# laserboard.net
KiCad netlist of a schematic drawn in EAGLE
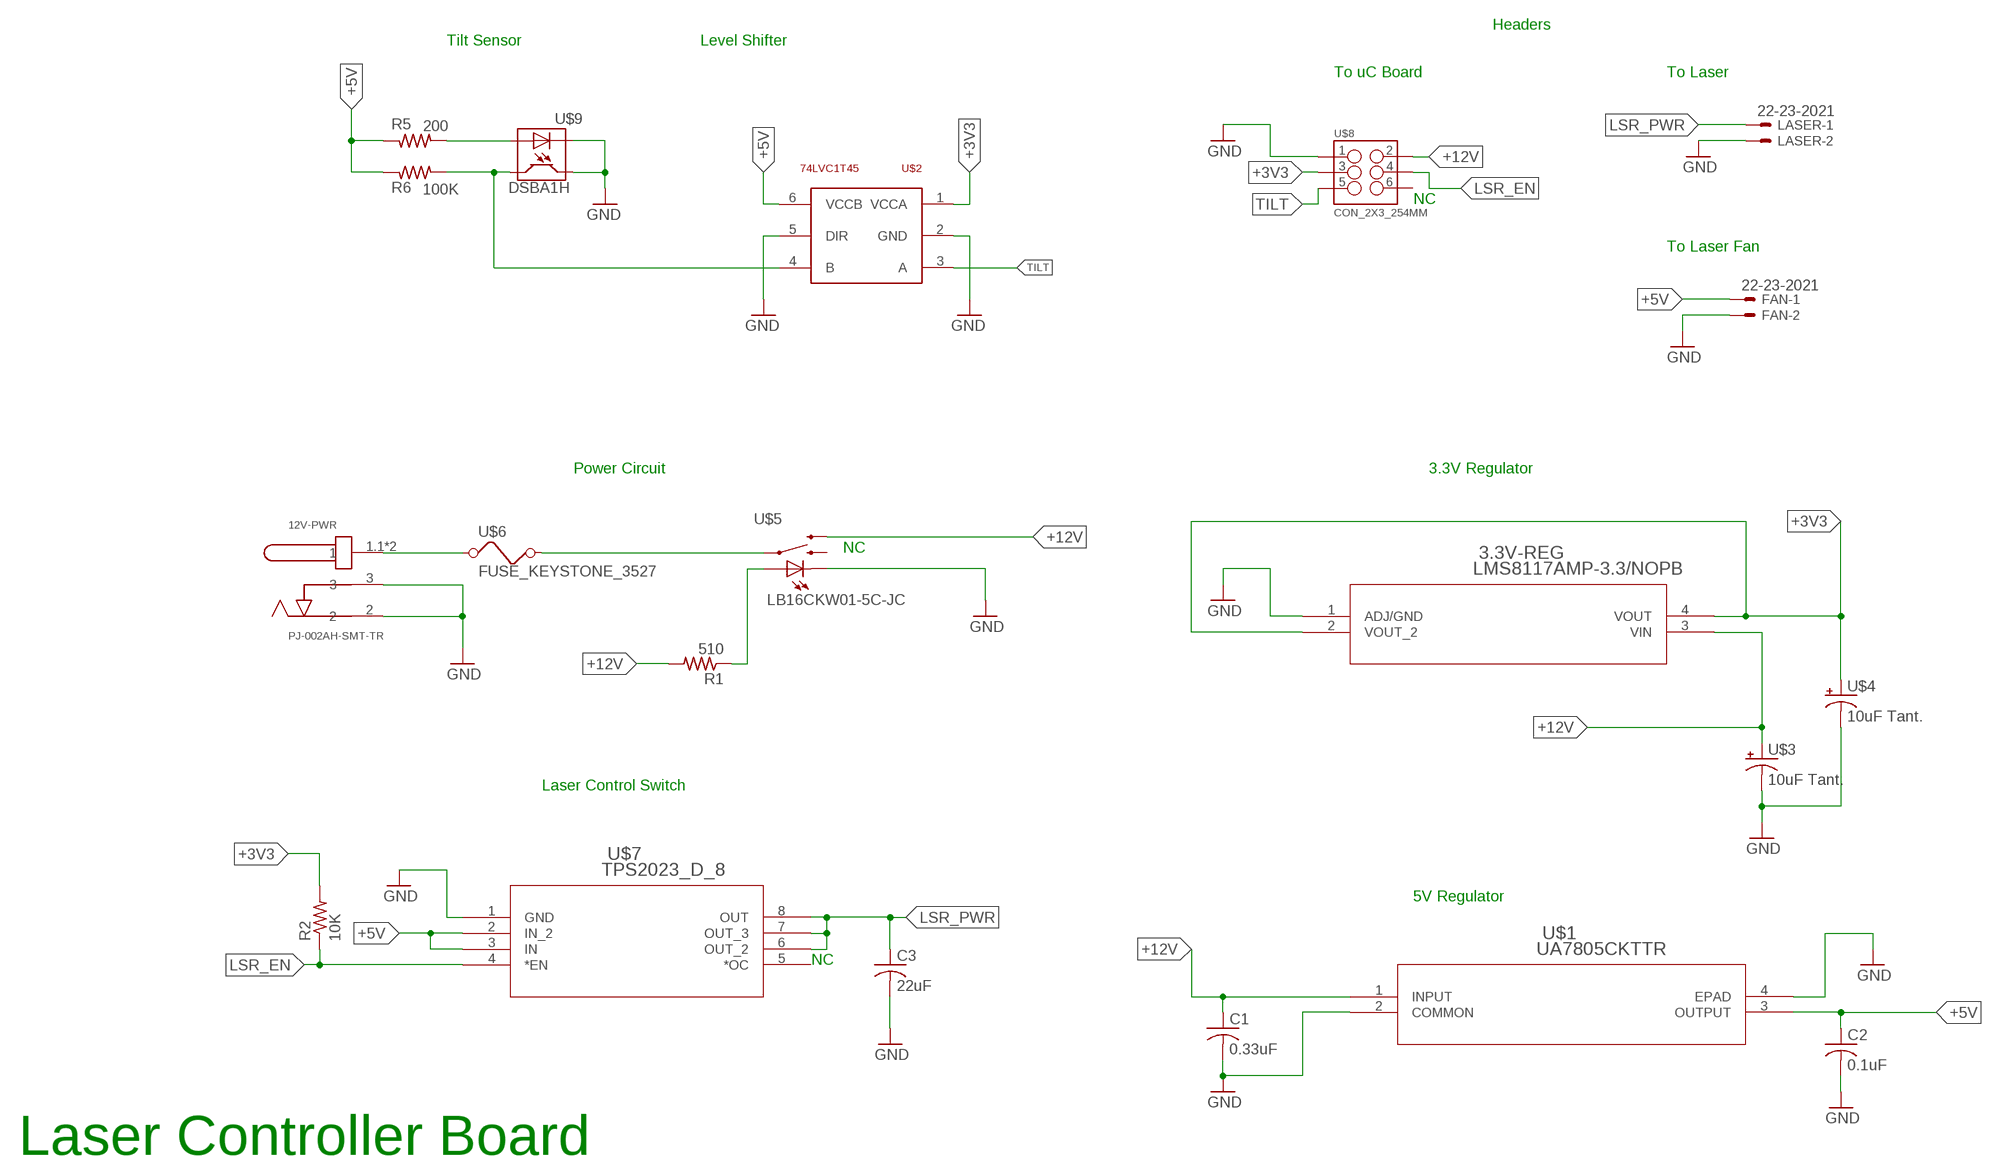
[diagram p0: schematic, sheet 1]

(export (version "E")
  (design (tool "Eeschema 10.0.6"))
  (components
    (comp (ref "3.3V-REG")
      (value "LMS8117AMP-3.3/NOPB")
      (footprint "eagle-import:MP04A")
      (fields
        (field (name "MANUFACTURER_PART_NUMBER") "LMS8117AMP-33")
        (field (name "COPYRIGHT") "Copyright (C) 2015 Accelerated Designs. All rights reserved")
      )
      (libsource (lib "eagle-import") (part "LMS8117AMP-3.3/NOPB"))
    )
    (comp (ref "12V-PWR")
      (value "PJ-002AH-SMT-TR")
      (footprint "eagle-import:CUI_PJ-002AH-SMT-TR")
      (libsource (lib "eagle-import") (part "PJ-002AH-SMT-TR"))
    )
    (comp (ref "C1")
      (value "0.33uF")
      (footprint "eagle-import:C0805")
      (libsource (lib "eagle-import") (part "C-USC0805"))
    )
    (comp (ref "C2")
      (value "0.1uF")
      (footprint "eagle-import:C0805")
      (libsource (lib "eagle-import") (part "C-USC0805"))
    )
    (comp (ref "C3")
      (value "22uF")
      (footprint "eagle-import:C0805")
      (libsource (lib "eagle-import") (part "C-USC0805"))
    )
    (comp (ref "FAN")
      (value "22-23-2021")
      (footprint "eagle-import:22-23-2021")
      (fields (field (name "MF") "MOLEX"))
      (libsource (lib "eagle-import") (part "22-23-2021"))
    )
    (comp (ref "LASER")
      (value "22-23-2021")
      (footprint "eagle-import:22-23-2021")
      (fields (field (name "MF") "MOLEX"))
      (libsource (lib "eagle-import") (part "22-23-2021"))
    )
    (comp (ref "R1")
      (value "510")
      (footprint "eagle-import:R0805")
      (libsource (lib "eagle-import") (part "R-US_R0805"))
    )
    (comp (ref "R2")
      (value "10K")
      (footprint "eagle-import:R0805")
      (libsource (lib "eagle-import") (part "R-US_R0805"))
    )
    (comp (ref "R5")
      (value "200")
      (footprint "eagle-import:R0805")
      (libsource (lib "eagle-import") (part "R-US_R0805"))
    )
    (comp (ref "R6")
      (value "100K")
      (footprint "eagle-import:R0805")
      (libsource (lib "eagle-import") (part "R-US_R0805"))
    )
    (comp (ref "U$1")
      (value "UA7805CKTTR")
      (footprint "eagle-import:KTT3_6P22X6P6")
      (fields
        (field (name "GENERIC_PART_NUMBER") "UA7805")
        (field (name "MANUFACTURER") "Texas Instruments")
        (field (name "MANUFACTURER_PART_NUMBER") "ua7805_ktt_3")
        (field (name "COPYRIGHT") "Copyright (C) 2015 Accelerated Designs. All rights reserved")
      )
      (libsource (lib "eagle-import") (part "UA7805CKTTR"))
    )
    (comp (ref "U$2")
      (value "74LVC1T45")
      (footprint "eagle-import:SOT363")
      (libsource (lib "eagle-import") (part "74LVC1T45"))
    )
    (comp (ref "U$3")
      (value "10uF Tant.")
      (footprint "eagle-import:C0805")
      (libsource (lib "eagle-import") (part "CAPACITOR_POL_0805"))
    )
    (comp (ref "U$4")
      (value "10uF Tant.")
      (footprint "eagle-import:C0805")
      (libsource (lib "eagle-import") (part "CAPACITOR_POL_0805"))
    )
    (comp (ref "U$5")
      (value "LB16CKW01-5C-JC")
      (footprint "eagle-import:LB16CKW01-5C-JC")
      (libsource (lib "eagle-import") (part "LB16CKW01-5C-JC"))
    )
    (comp (ref "U$6")
      (value "FUSE_KEYSTONE_3527")
      (footprint "eagle-import:KEYSTONE3527")
      (libsource (lib "eagle-import") (part "FUSE_KEYSTONE_3527"))
    )
    (comp (ref "U$7")
      (value "TPS2023_D_8")
      (footprint "eagle-import:D8")
      (fields
        (field (name "GENERIC_PART_NUMBER") "TPS2023")
        (field (name "MANUFACTURER") "Texas Instruments")
        (field (name "MANUFACTURER_PART_NUMBER") "tps2023_d_8")
        (field (name "COPYRIGHT") "Copyright (C) 2015 Accelerated Designs. All rights reserved")
      )
      (libsource (lib "eagle-import") (part "TPS2023_D_8"))
    )
    (comp (ref "U$8")
      (value "CON_2X3_254MM")
      (footprint "eagle-import:CON_2X3_254MM")
      (libsource (lib "eagle-import") (part "CON_2X3_254MM"))
    )
    (comp (ref "U$9")
      (value "DSBA1H")
      (footprint "eagle-import:DSBA1H")
      (libsource (lib "eagle-import") (part "DSBA1H"))
    )
  )
  (nets
    (net (code "1") (name "+3V3") (class "Default")
      (node (ref "3.3V-REG") (pin "2") (pinfunction "VOUT_2_2") (pintype "output"))
      (node (ref "3.3V-REG") (pin "4") (pinfunction "VOUT_4") (pintype "output"))
      (node (ref "R2") (pin "2") (pinfunction "2_2") (pintype "passive"))
      (node (ref "U$2") (pin "1") (pinfunction "VCCA_1") (pintype "bidirectional"))
      (node (ref "U$4") (pin "+") (pinfunction "+_+") (pintype "passive"))
      (node (ref "U$8") (pin "3") (pinfunction "3_3") (pintype "bidirectional"))
    )
    (net (code "2") (name "+5V") (class "Default")
      (node (ref "C2") (pin "1") (pinfunction "1_1") (pintype "passive"))
      (node (ref "FAN") (pin "1") (pinfunction "S_1") (pintype "passive"))
      (node (ref "R5") (pin "1") (pinfunction "1_1") (pintype "passive"))
      (node (ref "R6") (pin "1") (pinfunction "1_1") (pintype "passive"))
      (node (ref "U$1") (pin "3") (pinfunction "OUTPUT_3") (pintype "output"))
      (node (ref "U$2") (pin "6") (pinfunction "VCCB_6") (pintype "bidirectional"))
      (node (ref "U$7") (pin "2") (pinfunction "IN_2_2") (pintype "input"))
      (node (ref "U$7") (pin "3") (pinfunction "IN_3") (pintype "input"))
    )
    (net (code "3") (name "+12V") (class "Default")
      (node (ref "3.3V-REG") (pin "3") (pinfunction "VIN_3") (pintype "input"))
      (node (ref "C1") (pin "1") (pinfunction "1_1") (pintype "passive"))
      (node (ref "R1") (pin "2") (pinfunction "2_2") (pintype "passive"))
      (node (ref "U$1") (pin "1") (pinfunction "INPUT_1") (pintype "input"))
      (node (ref "U$3") (pin "+") (pinfunction "+_+") (pintype "passive"))
      (node (ref "U$5") (pin "2") (pinfunction "2_2") (pintype "passive"))
      (node (ref "U$8") (pin "2") (pinfunction "2_2") (pintype "bidirectional"))
    )
    (net (code "4") (name "GND") (class "Default")
      (node (ref "12V-PWR") (pin "2") (pinfunction "2_2") (pintype "passive"))
      (node (ref "12V-PWR") (pin "3") (pinfunction "3_3") (pintype "passive"))
      (node (ref "3.3V-REG") (pin "1") (pinfunction "ADJ/GND_1") (pintype "passive"))
      (node (ref "C1") (pin "2") (pinfunction "2_2") (pintype "passive"))
      (node (ref "C2") (pin "2") (pinfunction "2_2") (pintype "passive"))
      (node (ref "C3") (pin "2") (pinfunction "2_2") (pintype "passive"))
      (node (ref "FAN") (pin "2") (pinfunction "S_2") (pintype "passive"))
      (node (ref "LASER") (pin "2") (pinfunction "S_2") (pintype "passive"))
      (node (ref "U$1") (pin "2") (pinfunction "COMMON_2") (pintype "power_in"))
      (node (ref "U$1") (pin "4") (pinfunction "EPAD_4") (pintype "passive"))
      (node (ref "U$2") (pin "2") (pinfunction "GND_2") (pintype "bidirectional"))
      (node (ref "U$2") (pin "5") (pinfunction "DIR_5") (pintype "bidirectional"))
      (node (ref "U$3") (pin "-") (pinfunction "-_-") (pintype "passive"))
      (node (ref "U$4") (pin "-") (pinfunction "-_-") (pintype "passive"))
      (node (ref "U$5") (pin "-") (pinfunction "-_-") (pintype "passive"))
      (node (ref "U$7") (pin "1") (pinfunction "GND_1") (pintype "input"))
      (node (ref "U$8") (pin "1") (pinfunction "1_1") (pintype "bidirectional"))
      (node (ref "U$9") (pin "-") (pinfunction "-_-") (pintype "passive"))
      (node (ref "U$9") (pin "E") (pinfunction "E_E") (pintype "passive"))
    )
    (net (code "5") (name "LSR_EN") (class "Default")
      (node (ref "R2") (pin "1") (pinfunction "1_1") (pintype "passive"))
      (node (ref "U$7") (pin "4") (pinfunction "*EN_4") (pintype "input"))
      (node (ref "U$8") (pin "4") (pinfunction "4_4") (pintype "bidirectional"))
    )
    (net (code "6") (name "LSR_PWR") (class "Default")
      (node (ref "C3") (pin "1") (pinfunction "1_1") (pintype "passive"))
      (node (ref "LASER") (pin "1") (pinfunction "S_1") (pintype "passive"))
      (node (ref "U$7") (pin "6") (pinfunction "OUT_2_6") (pintype "output"))
      (node (ref "U$7") (pin "7") (pinfunction "OUT_3_7") (pintype "output"))
      (node (ref "U$7") (pin "8") (pinfunction "OUT_8") (pintype "output"))
    )
    (net (code "7") (name "Net-(R1-Pad1)") (class "Default")
      (node (ref "R1") (pin "1") (pinfunction "1_1") (pintype "passive"))
      (node (ref "U$5") (pin "+") (pinfunction "+_+") (pintype "passive"))
    )
    (net (code "8") (name "Net-(R5-Pad2)") (class "Default")
      (node (ref "R5") (pin "2") (pinfunction "2_2") (pintype "passive"))
      (node (ref "U$9") (pin "+") (pinfunction "+_+") (pintype "passive"))
    )
    (net (code "9") (name "Net-(U$2-B)") (class "Default")
      (node (ref "R6") (pin "2") (pinfunction "2_2") (pintype "passive"))
      (node (ref "U$2") (pin "4") (pinfunction "B_4") (pintype "bidirectional"))
      (node (ref "U$9") (pin "C") (pinfunction "C_C") (pintype "passive"))
    )
    (net (code "10") (name "Net-(U$6-1)") (class "Default")
      (node (ref "12V-PWR") (pin "1.1") (pinfunction "1_1.1") (pintype "passive"))
      (node (ref "12V-PWR") (pin "1.2") (pinfunction "1_1.2") (pintype "passive"))
      (node (ref "U$6") (pin "P$1") (pinfunction "1_P$1") (pintype "passive"))
    )
    (net (code "11") (name "Net-(U$6-2)") (class "Default")
      (node (ref "U$5") (pin "1") (pinfunction "1_1") (pintype "passive"))
      (node (ref "U$6") (pin "P$2") (pinfunction "2_P$2") (pintype "passive"))
    )
    (net (code "12") (name "TILT") (class "Default")
      (node (ref "U$2") (pin "3") (pinfunction "A_3") (pintype "bidirectional"))
      (node (ref "U$8") (pin "5") (pinfunction "5_5") (pintype "bidirectional"))
    )
    (net (code "13") (name "unconnected-(U$5-Pad3)") (class "Default")
      (node (ref "U$5") (pin "3") (pinfunction "3_3") (pintype "passive"))
    )
    (net (code "14") (name "unconnected-(U$7-*OC-Pad5)") (class "Default")
      (node (ref "U$7") (pin "5") (pinfunction "*OC_5") (pintype "output"))
    )
    (net (code "15") (name "unconnected-(U$8-Pad6)") (class "Default")
      (node (ref "U$8") (pin "6") (pinfunction "6_6") (pintype "bidirectional"))
    )
  )
)
